# Main.net
KiCad netlist of a schematic drawn in Altium Designer
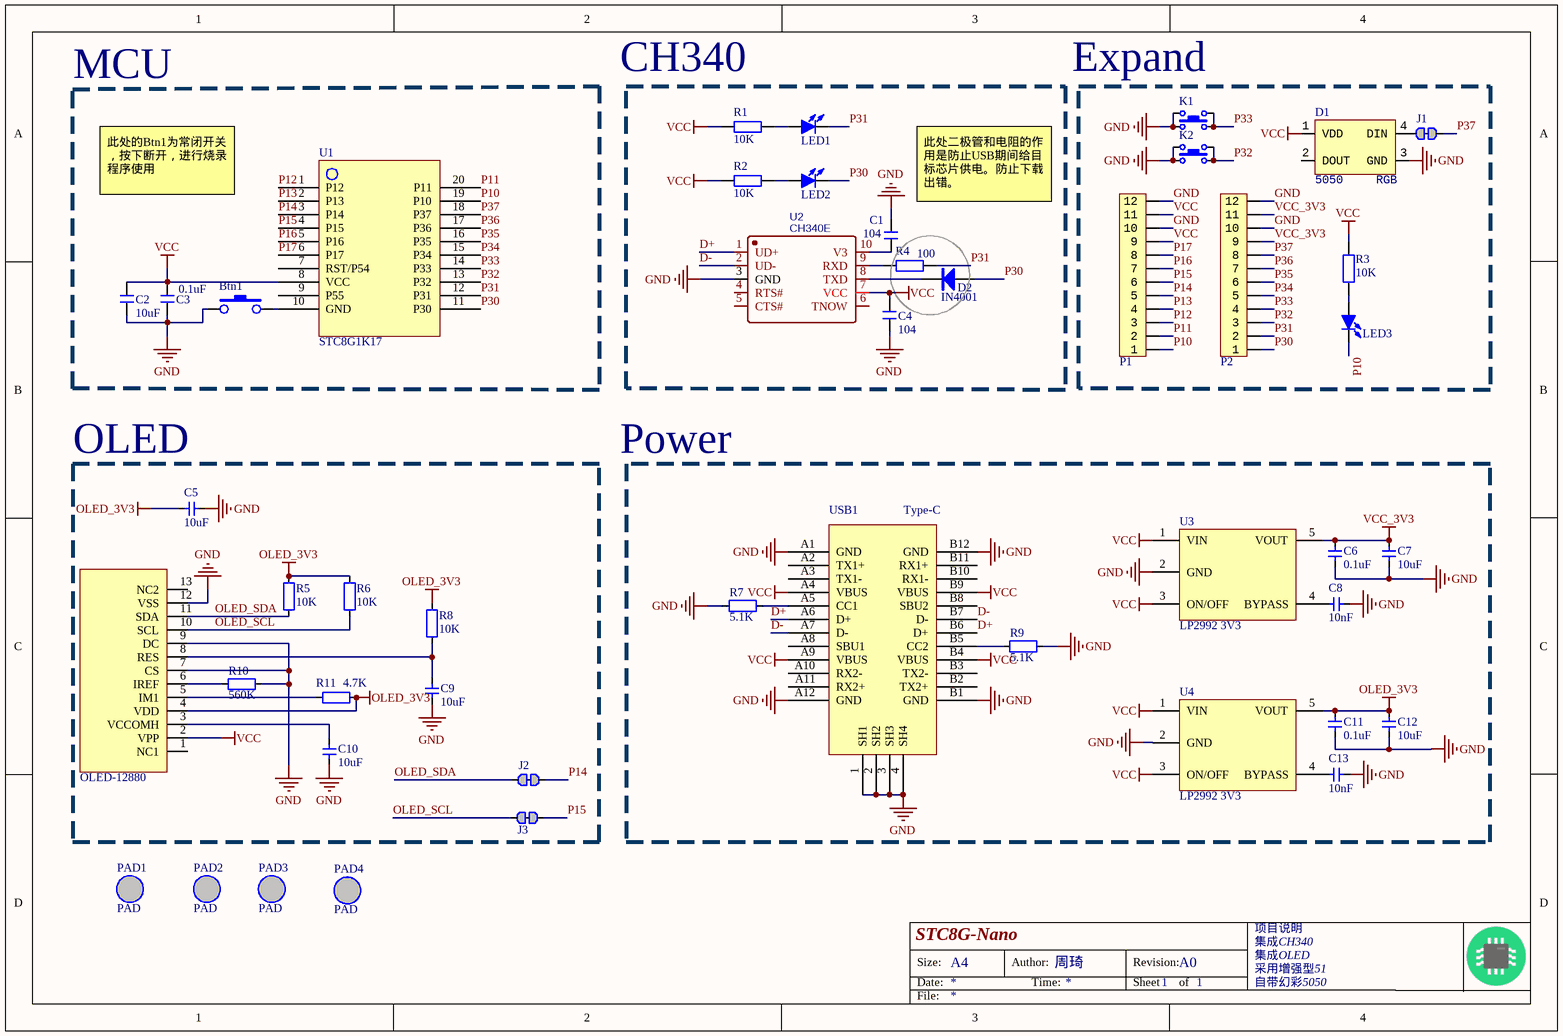
[diagram p0: Main.SchDoc]

(export (version "E")
  (design (tool "Eeschema 10.0.6"))
  (components
    (comp (ref "1")
      (value "OLED-12880")
      (footprint "OLED-12880")
      (libsource (lib "mLib") (part "OLED-12880"))
    )
    (comp (ref "Btn1") (value "KEY") (footprint "TSW SMD-3*6*2.5") (libsource (lib "常用元件库") (part "KEY")))
    (comp (ref "C1")
      (value "104")
      (footprint "C0402_L")
      (description "无极性贴片电容")
      (fields (field (name "版权归属") "源创客"))
      (libsource (lib "9-电阻-电容-电感") (part "C"))
    )
    (comp (ref "C2")
      (value "10uF")
      (footprint "C0402_L")
      (description "无极性贴片电容")
      (fields (field (name "版权归属") "源创客"))
      (libsource (lib "9-电阻-电容-电感") (part "C"))
    )
    (comp (ref "C3")
      (value "0.1uF")
      (footprint "C0402_L")
      (description "无极性贴片电容")
      (fields (field (name "版权归属") "源创客"))
      (libsource (lib "9-电阻-电容-电感") (part "C"))
    )
    (comp (ref "C4")
      (value "104")
      (footprint "C0402_L")
      (description "无极性贴片电容")
      (fields (field (name "版权归属") "源创客"))
      (libsource (lib "9-电阻-电容-电感") (part "C"))
    )
    (comp (ref "C5")
      (value "10uF")
      (footprint "CAP_0402")
      (description "Capacitor")
      (libsource (lib "MyPcbLib") (part "电容-0402"))
    )
    (comp (ref "C6")
      (value "0.1uF")
      (footprint "CAP_0402")
      (description "Capacitor")
      (libsource (lib "MyPcbLib") (part "电容-0402"))
    )
    (comp (ref "C7")
      (value "10uF")
      (footprint "CAP_0402")
      (description "Capacitor")
      (libsource (lib "MyPcbLib") (part "电容-0402"))
    )
    (comp (ref "C8")
      (value "10nF")
      (footprint "CAP_0402")
      (description "Capacitor")
      (libsource (lib "MyPcbLib") (part "电容-0402"))
    )
    (comp (ref "C9")
      (value "10uF")
      (footprint "CAP_0402")
      (description "Capacitor")
      (libsource (lib "MyPcbLib") (part "电容-0402"))
    )
    (comp (ref "C10")
      (value "10uF")
      (footprint "CAP_0402")
      (description "Capacitor")
      (libsource (lib "MyPcbLib") (part "电容-0402"))
    )
    (comp (ref "C11")
      (value "0.1uF")
      (footprint "CAP_0402")
      (description "Capacitor")
      (libsource (lib "MyPcbLib") (part "电容-0402"))
    )
    (comp (ref "C12")
      (value "10uF")
      (footprint "CAP_0402")
      (description "Capacitor")
      (libsource (lib "MyPcbLib") (part "电容-0402"))
    )
    (comp (ref "C13")
      (value "10nF")
      (footprint "CAP_0402")
      (description "Capacitor")
      (libsource (lib "MyPcbLib") (part "电容-0402"))
    )
    (comp (ref "D1")
      (value "RGB")
      (footprint "LED_5050_WS2812B")
      (description "LED")
      (fields (field (name "TYPE") "5050"))
      (libsource (lib "KitSprout") (part "LED_5050_WS2812B"))
    )
    (comp (ref "D2")
      (value "IN4001")
      (footprint "SOD-323")
      (description "整流二极管")
      (fields (field (name "版权归属") "源创客"))
      (libsource (lib "10-二极管-整流桥") (part "M7"))
    )
    (comp (ref "J1")
      (value "跳线")
      (footprint "RES_0402")
      (description "Resistor")
      (fields (field (name "PUBLISHER") "Altium Limited"))
      (libsource (lib "MyPcbLib") (part "跳线"))
    )
    (comp (ref "J2")
      (value "跳线")
      (footprint "RES_0402")
      (description "Resistor")
      (fields (field (name "PUBLISHER") "Altium Limited"))
      (libsource (lib "MyPcbLib") (part "跳线"))
    )
    (comp (ref "J3")
      (value "跳线")
      (footprint "RES_0402")
      (description "Resistor")
      (fields (field (name "PUBLISHER") "Altium Limited"))
      (libsource (lib "MyPcbLib") (part "跳线"))
    )
    (comp (ref "K1")
      (value "TACT 4P")
      (footprint "ButtonTACT_3.5*3.55_90")
      (description "Button")
      (libsource (lib "KitSprout") (part "ButtonTACT"))
    )
    (comp (ref "K2")
      (value "TACT 4P")
      (footprint "ButtonTACT_3.5*3.55_90")
      (description "Button")
      (libsource (lib "KitSprout") (part "ButtonTACT"))
    )
    (comp (ref "LED1")
      (value "红色")
      (footprint "LED0603_B")
      (description "贴片LED")
      (libsource (lib "0.3 - LED发光二极管") (part "LED-SMD"))
    )
    (comp (ref "LED2")
      (value "红色")
      (footprint "LED0603_B")
      (description "贴片LED")
      (libsource (lib "0.3 - LED发光二极管") (part "LED-SMD"))
    )
    (comp (ref "LED3")
      (value "红色")
      (footprint "LED0603_B")
      (description "贴片LED")
      (libsource (lib "0.3 - LED发光二极管") (part "LED-SMD"))
    )
    (comp (ref "P1")
      (value "HDR1x12_2.54")
      (footprint "HDR2.54-LI-12P")
      (description "Header")
      (libsource (lib "KitSprout") (part "HDR1x12_2.54"))
    )
    (comp (ref "P2")
      (value "HDR1x12_2.54")
      (footprint "HDR2.54-LI-12P")
      (description "Header")
      (libsource (lib "KitSprout") (part "HDR1x12_2.54"))
    )
    (comp (ref "PAD1")
      (value "PAD")
      (footprint "M2")
      (description "M2通孔")
      (libsource (lib "原理图库") (part "PAD"))
    )
    (comp (ref "PAD2")
      (value "PAD")
      (footprint "M2")
      (description "M2通孔")
      (libsource (lib "原理图库") (part "PAD"))
    )
    (comp (ref "PAD3")
      (value "PAD")
      (footprint "M2")
      (description "M2通孔")
      (libsource (lib "原理图库") (part "PAD"))
    )
    (comp (ref "PAD4")
      (value "PAD")
      (footprint "M2")
      (description "M2通孔")
      (libsource (lib "原理图库") (part "PAD"))
    )
    (comp (ref "R1")
      (value "10K")
      (footprint "RES_0402")
      (description "直插色环电阻")
      (fields (field (name "版权归属") "源创客"))
      (libsource (lib "9-电阻-电容-电感") (part "R-CRR"))
    )
    (comp (ref "R2")
      (value "10K")
      (footprint "RES_0402")
      (description "直插色环电阻")
      (fields (field (name "版权归属") "源创客"))
      (libsource (lib "9-电阻-电容-电感") (part "R-CRR"))
    )
    (comp (ref "R3")
      (value "10K")
      (footprint "RES_0402")
      (description "直插色环电阻")
      (fields (field (name "版权归属") "源创客"))
      (libsource (lib "9-电阻-电容-电感") (part "R-CRR"))
    )
    (comp (ref "R4")
      (value "100")
      (footprint "RES_0402")
      (description "直插色环电阻")
      (fields (field (name "版权归属") "源创客"))
      (libsource (lib "9-电阻-电容-电感") (part "R-CRR"))
    )
    (comp (ref "R5")
      (value "10K")
      (footprint "RES_0402")
      (description "Resistor")
      (libsource (lib "MyPcbLib") (part "电阻-0402"))
    )
    (comp (ref "R6")
      (value "10K")
      (footprint "RES_0402")
      (description "Resistor")
      (libsource (lib "MyPcbLib") (part "电阻-0402"))
    )
    (comp (ref "R7")
      (value "5.1K")
      (footprint "RES_0402")
      (description "Resistor")
      (libsource (lib "") (part "电阻-0402_1"))
    )
    (comp (ref "R8")
      (value "10K")
      (footprint "RES_0402")
      (description "Resistor")
      (libsource (lib "MyPcbLib") (part "电阻-0402"))
    )
    (comp (ref "R9")
      (value "5.1K")
      (footprint "RES_0402")
      (description "Resistor")
      (libsource (lib "") (part "电阻-0402_2"))
    )
    (comp (ref "R10")
      (value "560K")
      (footprint "RES_0402")
      (description "Resistor")
      (libsource (lib "") (part "电阻-0402_1"))
    )
    (comp (ref "R11")
      (value "4.7K")
      (footprint "RES_0402")
      (description "Resistor")
      (libsource (lib "") (part "电阻-0402_1"))
    )
    (comp (ref "U1") (value "STC8G1K17") (footprint "TSSOP20_L") (libsource (lib "原理图库") (part "STC8G1K17")))
    (comp (ref "U2")
      (value "CH340E")
      (footprint "MSOP10_M")
      (fields (field (name "BOM_SUPPLIER PART") "C99652") (field (name "SUBPART_NO") "1"))
      (libsource (lib "altium-import") (part "root_0_CH340E_"))
    )
    (comp (ref "U3")
      (value "LP2992 3V3")
      (footprint "SOT23-5")
      (description "LDO")
      (libsource (lib "MyPcbLib") (part "LP2992"))
    )
    (comp (ref "U4")
      (value "LP2992 3V3")
      (footprint "SOT23-5")
      (description "LDO")
      (libsource (lib "MyPcbLib") (part "LP2992"))
    )
    (comp (ref "USB1")
      (value "Type-C")
      (footprint "USB-C-SMD_16P")
      (libsource (lib "MyPcbLib") (part "USB-Type-C-TOP"))
    )
  )
  (nets
    (net (code "1") (name "/D+") (class "Default")
      (node (ref "U2") (pin "1") (pinfunction "UD+_1") (pintype "passive"))
      (node (ref "USB1") (pin "A6") (pinfunction "D+_A6") (pintype "passive"))
      (node (ref "USB1") (pin "B6") (pinfunction "D+_B6") (pintype "passive"))
    )
    (net (code "2") (name "/D-") (class "Default")
      (node (ref "U2") (pin "2") (pinfunction "UD-_2") (pintype "passive"))
      (node (ref "USB1") (pin "A7") (pinfunction "D-_A7") (pintype "passive"))
      (node (ref "USB1") (pin "B7") (pinfunction "D-_B7") (pintype "passive"))
    )
    (net (code "3") (name "/OLED_SCL") (class "Default")
      (node (ref "1") (pin "10") (pinfunction "SCL_10") (pintype "passive"))
      (node (ref "J3") (pin "1") (pinfunction "1_1") (pintype "passive"))
      (node (ref "R6") (pin "1") (pinfunction "1_1") (pintype "passive"))
    )
    (net (code "4") (name "/OLED_SDA") (class "Default")
      (node (ref "1") (pin "11") (pinfunction "SDA_11") (pintype "passive"))
      (node (ref "J2") (pin "1") (pinfunction "1_1") (pintype "passive"))
      (node (ref "R5") (pin "1") (pinfunction "1_1") (pintype "passive"))
    )
    (net (code "5") (name "/P10") (class "Default")
      (node (ref "LED3") (pin "2") (pinfunction "K_2") (pintype "passive"))
      (node (ref "P1") (pin "1") (pinfunction "1_1") (pintype "passive"))
      (node (ref "U1") (pin "19") (pinfunction "P10_19") (pintype "passive"))
    )
    (net (code "6") (name "/P11") (class "Default")
      (node (ref "P1") (pin "2") (pinfunction "2_2") (pintype "passive"))
      (node (ref "U1") (pin "20") (pinfunction "P11_20") (pintype "passive"))
    )
    (net (code "7") (name "/P12") (class "Default")
      (node (ref "P1") (pin "3") (pinfunction "3_3") (pintype "passive"))
      (node (ref "U1") (pin "1") (pinfunction "P12_1") (pintype "passive"))
    )
    (net (code "8") (name "/P13") (class "Default")
      (node (ref "P1") (pin "4") (pinfunction "4_4") (pintype "passive"))
      (node (ref "U1") (pin "2") (pinfunction "P13_2") (pintype "passive"))
    )
    (net (code "9") (name "/P14") (class "Default")
      (node (ref "J2") (pin "2") (pinfunction "2_2") (pintype "passive"))
      (node (ref "P1") (pin "5") (pinfunction "5_5") (pintype "passive"))
      (node (ref "U1") (pin "3") (pinfunction "P14_3") (pintype "passive"))
    )
    (net (code "10") (name "/P15") (class "Default")
      (node (ref "J3") (pin "2") (pinfunction "2_2") (pintype "passive"))
      (node (ref "P1") (pin "6") (pinfunction "6_6") (pintype "passive"))
      (node (ref "U1") (pin "4") (pinfunction "P15_4") (pintype "passive"))
    )
    (net (code "11") (name "/P16") (class "Default")
      (node (ref "P1") (pin "7") (pinfunction "7_7") (pintype "passive"))
      (node (ref "U1") (pin "5") (pinfunction "P16_5") (pintype "passive"))
    )
    (net (code "12") (name "/P17") (class "Default")
      (node (ref "P1") (pin "8") (pinfunction "8_8") (pintype "passive"))
      (node (ref "U1") (pin "6") (pinfunction "P17_6") (pintype "passive"))
    )
    (net (code "13") (name "/P30") (class "Default")
      (node (ref "D2") (pin "1") (pinfunction "A_1") (pintype "passive"))
      (node (ref "LED2") (pin "2") (pinfunction "K_2") (pintype "passive"))
      (node (ref "P2") (pin "1") (pinfunction "1_1") (pintype "passive"))
      (node (ref "U1") (pin "11") (pinfunction "P30_11") (pintype "passive"))
    )
    (net (code "14") (name "/P31") (class "Default")
      (node (ref "LED1") (pin "2") (pinfunction "K_2") (pintype "passive"))
      (node (ref "P2") (pin "2") (pinfunction "2_2") (pintype "passive"))
      (node (ref "R4") (pin "1") (pinfunction "1_1") (pintype "passive"))
      (node (ref "U1") (pin "12") (pinfunction "P31_12") (pintype "passive"))
    )
    (net (code "15") (name "/P32") (class "Default")
      (node (ref "K2") (pin "2") (pinfunction "2_2") (pintype "passive"))
      (node (ref "K2") (pin "4") (pinfunction "4_4") (pintype "passive"))
      (node (ref "P2") (pin "3") (pinfunction "3_3") (pintype "passive"))
      (node (ref "U1") (pin "13") (pinfunction "P32_13") (pintype "passive"))
    )
    (net (code "16") (name "/P33") (class "Default")
      (node (ref "K1") (pin "2") (pinfunction "2_2") (pintype "passive"))
      (node (ref "K1") (pin "4") (pinfunction "4_4") (pintype "passive"))
      (node (ref "P2") (pin "4") (pinfunction "4_4") (pintype "passive"))
      (node (ref "U1") (pin "14") (pinfunction "P33_14") (pintype "passive"))
    )
    (net (code "17") (name "/P34") (class "Default")
      (node (ref "P2") (pin "5") (pinfunction "5_5") (pintype "passive"))
      (node (ref "U1") (pin "15") (pinfunction "P34_15") (pintype "passive"))
    )
    (net (code "18") (name "/P35") (class "Default")
      (node (ref "P2") (pin "6") (pinfunction "6_6") (pintype "passive"))
      (node (ref "U1") (pin "16") (pinfunction "P35_16") (pintype "passive"))
    )
    (net (code "19") (name "/P36") (class "Default")
      (node (ref "P2") (pin "7") (pinfunction "7_7") (pintype "passive"))
      (node (ref "U1") (pin "17") (pinfunction "P36_17") (pintype "passive"))
    )
    (net (code "20") (name "/P37") (class "Default")
      (node (ref "J1") (pin "2") (pinfunction "2_2") (pintype "passive"))
      (node (ref "P2") (pin "8") (pinfunction "8_8") (pintype "passive"))
      (node (ref "U1") (pin "18") (pinfunction "P37_18") (pintype "passive"))
    )
    (net (code "21") (name "GND") (class "Default")
      (node (ref "1") (pin "12") (pinfunction "VSS_12") (pintype "passive"))
      (node (ref "1") (pin "7") (pinfunction "CS_7") (pintype "passive"))
      (node (ref "1") (pin "9") (pinfunction "DC_9") (pintype "passive"))
      (node (ref "Btn1") (pin "1") (pinfunction "1_1") (pintype "passive"))
      (node (ref "C1") (pin "1") (pinfunction "1_1") (pintype "passive"))
      (node (ref "C10") (pin "1") (pinfunction "1_1") (pintype "passive"))
      (node (ref "C11") (pin "1") (pinfunction "1_1") (pintype "passive"))
      (node (ref "C12") (pin "1") (pinfunction "1_1") (pintype "passive"))
      (node (ref "C13") (pin "1") (pinfunction "1_1") (pintype "passive"))
      (node (ref "C2") (pin "1") (pinfunction "1_1") (pintype "passive"))
      (node (ref "C3") (pin "1") (pinfunction "1_1") (pintype "passive"))
      (node (ref "C4") (pin "2") (pinfunction "2_2") (pintype "passive"))
      (node (ref "C5") (pin "1") (pinfunction "1_1") (pintype "passive"))
      (node (ref "C6") (pin "1") (pinfunction "1_1") (pintype "passive"))
      (node (ref "C7") (pin "1") (pinfunction "1_1") (pintype "passive"))
      (node (ref "C8") (pin "1") (pinfunction "1_1") (pintype "passive"))
      (node (ref "C9") (pin "1") (pinfunction "1_1") (pintype "passive"))
      (node (ref "D1") (pin "3") (pinfunction "GND_3") (pintype "passive"))
      (node (ref "K1") (pin "1") (pinfunction "1_1") (pintype "passive"))
      (node (ref "K1") (pin "3") (pinfunction "3_3") (pintype "passive"))
      (node (ref "K2") (pin "1") (pinfunction "1_1") (pintype "passive"))
      (node (ref "K2") (pin "3") (pinfunction "3_3") (pintype "passive"))
      (node (ref "P1") (pin "10") (pinfunction "10_10") (pintype "passive"))
      (node (ref "P1") (pin "12") (pinfunction "12_12") (pintype "passive"))
      (node (ref "P2") (pin "10") (pinfunction "10_10") (pintype "passive"))
      (node (ref "P2") (pin "12") (pinfunction "12_12") (pintype "passive"))
      (node (ref "R10") (pin "2") (pinfunction "2_2") (pintype "passive"))
      (node (ref "R7") (pin "1") (pinfunction "1_1") (pintype "passive"))
      (node (ref "R9") (pin "1") (pinfunction "1_1") (pintype "passive"))
      (node (ref "U2") (pin "3") (pinfunction "GND_3") (pintype "passive"))
      (node (ref "U3") (pin "2") (pinfunction "GND_2") (pintype "passive"))
      (node (ref "U4") (pin "2") (pinfunction "GND_2") (pintype "passive"))
      (node (ref "USB1") (pin "1") (pinfunction "SH1_1") (pintype "passive"))
      (node (ref "USB1") (pin "2") (pinfunction "SH2_2") (pintype "passive"))
      (node (ref "USB1") (pin "3") (pinfunction "SH3_3") (pintype "passive"))
      (node (ref "USB1") (pin "4") (pinfunction "SH4_4") (pintype "passive"))
      (node (ref "USB1") (pin "A1") (pinfunction "GND_A1") (pintype "passive"))
      (node (ref "USB1") (pin "A12") (pinfunction "GND_A12") (pintype "passive"))
      (node (ref "USB1") (pin "B1") (pinfunction "GND_B1") (pintype "passive"))
      (node (ref "USB1") (pin "B12") (pinfunction "GND_B12") (pintype "passive"))
    )
    (net (code "22") (name "Net-(1-IM1)") (class "Default")
      (node (ref "1") (pin "5") (pinfunction "IM1_5") (pintype "passive"))
      (node (ref "R11") (pin "1") (pinfunction "1_1") (pintype "passive"))
    )
    (net (code "23") (name "Net-(1-IREF)") (class "Default")
      (node (ref "1") (pin "6") (pinfunction "IREF_6") (pintype "passive"))
      (node (ref "R10") (pin "1") (pinfunction "1_1") (pintype "passive"))
    )
    (net (code "24") (name "Net-(1-RES)") (class "Default")
      (node (ref "1") (pin "8") (pinfunction "RES_8") (pintype "passive"))
      (node (ref "C9") (pin "2") (pinfunction "2_2") (pintype "passive"))
      (node (ref "R8") (pin "1") (pinfunction "1_1") (pintype "passive"))
    )
    (net (code "25") (name "Net-(1-VCCOMH)") (class "Default")
      (node (ref "1") (pin "3") (pinfunction "VCCOMH_3") (pintype "passive"))
      (node (ref "C10") (pin "2") (pinfunction "2_2") (pintype "passive"))
    )
    (net (code "26") (name "Net-(D1-DIN)") (class "Default")
      (node (ref "D1") (pin "4") (pinfunction "DIN_4") (pintype "passive"))
      (node (ref "J1") (pin "1") (pinfunction "1_1") (pintype "passive"))
    )
    (net (code "27") (name "Net-(D2-K)") (class "Default")
      (node (ref "D2") (pin "2") (pinfunction "K_2") (pintype "passive"))
      (node (ref "U2") (pin "8") (pinfunction "TXD_8") (pintype "passive"))
    )
    (net (code "28") (name "Net-(LED1-A)") (class "Default")
      (node (ref "LED1") (pin "1") (pinfunction "A_1") (pintype "passive"))
      (node (ref "R1") (pin "1") (pinfunction "1_1") (pintype "passive"))
    )
    (net (code "29") (name "Net-(LED2-A)") (class "Default")
      (node (ref "LED2") (pin "1") (pinfunction "A_1") (pintype "passive"))
      (node (ref "R2") (pin "1") (pinfunction "1_1") (pintype "passive"))
    )
    (net (code "30") (name "Net-(LED3-A)") (class "Default")
      (node (ref "LED3") (pin "1") (pinfunction "A_1") (pintype "passive"))
      (node (ref "R3") (pin "1") (pinfunction "1_1") (pintype "passive"))
    )
    (net (code "31") (name "Net-(U1-GND)") (class "Default")
      (node (ref "Btn1") (pin "2") (pinfunction "2_2") (pintype "passive"))
      (node (ref "U1") (pin "10") (pinfunction "GND_10") (pintype "passive"))
    )
    (net (code "32") (name "Net-(U2-RXD)") (class "Default")
      (node (ref "R4") (pin "2") (pinfunction "2_2") (pintype "passive"))
      (node (ref "U2") (pin "9") (pinfunction "RXD_9") (pintype "passive"))
    )
    (net (code "33") (name "Net-(U2-V3)") (class "Default")
      (node (ref "C1") (pin "2") (pinfunction "2_2") (pintype "passive"))
      (node (ref "U2") (pin "10") (pinfunction "V3_10") (pintype "passive"))
    )
    (net (code "34") (name "Net-(U3-BYPASS)") (class "Default")
      (node (ref "C8") (pin "2") (pinfunction "2_2") (pintype "passive"))
      (node (ref "U3") (pin "4") (pinfunction "BYPASS_4") (pintype "passive"))
    )
    (net (code "35") (name "Net-(U4-BYPASS)") (class "Default")
      (node (ref "C13") (pin "2") (pinfunction "2_2") (pintype "passive"))
      (node (ref "U4") (pin "4") (pinfunction "BYPASS_4") (pintype "passive"))
    )
    (net (code "36") (name "Net-(USB1-CC1)") (class "Default")
      (node (ref "R7") (pin "2") (pinfunction "2_2") (pintype "passive"))
      (node (ref "USB1") (pin "A5") (pinfunction "CC1_A5") (pintype "passive"))
    )
    (net (code "37") (name "Net-(USB1-CC2)") (class "Default")
      (node (ref "R9") (pin "2") (pinfunction "2_2") (pintype "passive"))
      (node (ref "USB1") (pin "B5") (pinfunction "CC2_B5") (pintype "passive"))
    )
    (net (code "38") (name "OLED_3V3") (class "Default")
      (node (ref "1") (pin "4") (pinfunction "VDD_4") (pintype "passive"))
      (node (ref "C11") (pin "2") (pinfunction "2_2") (pintype "passive"))
      (node (ref "C12") (pin "2") (pinfunction "2_2") (pintype "passive"))
      (node (ref "C5") (pin "2") (pinfunction "2_2") (pintype "passive"))
      (node (ref "R11") (pin "2") (pinfunction "2_2") (pintype "passive"))
      (node (ref "R5") (pin "2") (pinfunction "2_2") (pintype "passive"))
      (node (ref "R6") (pin "2") (pinfunction "2_2") (pintype "passive"))
      (node (ref "R8") (pin "2") (pinfunction "2_2") (pintype "passive"))
      (node (ref "U4") (pin "5") (pinfunction "VOUT_5") (pintype "passive"))
    )
    (net (code "39") (name "VCC") (class "Default")
      (node (ref "1") (pin "2") (pinfunction "VPP_2") (pintype "passive"))
      (node (ref "C2") (pin "2") (pinfunction "2_2") (pintype "passive"))
      (node (ref "C3") (pin "2") (pinfunction "2_2") (pintype "passive"))
      (node (ref "C4") (pin "1") (pinfunction "1_1") (pintype "passive"))
      (node (ref "D1") (pin "1") (pinfunction "VDD_1") (pintype "passive"))
      (node (ref "P1") (pin "11") (pinfunction "11_11") (pintype "passive"))
      (node (ref "P1") (pin "9") (pinfunction "9_9") (pintype "passive"))
      (node (ref "R1") (pin "2") (pinfunction "2_2") (pintype "passive"))
      (node (ref "R2") (pin "2") (pinfunction "2_2") (pintype "passive"))
      (node (ref "R3") (pin "2") (pinfunction "2_2") (pintype "passive"))
      (node (ref "U1") (pin "8") (pinfunction "VCC_8") (pintype "passive"))
      (node (ref "U2") (pin "7") (pinfunction "VCC_7") (pintype "passive"))
      (node (ref "U3") (pin "1") (pinfunction "VIN_1") (pintype "passive"))
      (node (ref "U3") (pin "3") (pinfunction "ON/OFF_3") (pintype "passive"))
      (node (ref "U4") (pin "1") (pinfunction "VIN_1") (pintype "passive"))
      (node (ref "U4") (pin "3") (pinfunction "ON/OFF_3") (pintype "passive"))
      (node (ref "USB1") (pin "A4") (pinfunction "VBUS_A4") (pintype "passive"))
      (node (ref "USB1") (pin "A9") (pinfunction "VBUS_A9") (pintype "passive"))
      (node (ref "USB1") (pin "B4") (pinfunction "VBUS_B4") (pintype "passive"))
      (node (ref "USB1") (pin "B9") (pinfunction "VBUS_B9") (pintype "passive"))
    )
    (net (code "40") (name "VCC_3V3") (class "Default")
      (node (ref "C6") (pin "2") (pinfunction "2_2") (pintype "passive"))
      (node (ref "C7") (pin "2") (pinfunction "2_2") (pintype "passive"))
      (node (ref "P2") (pin "11") (pinfunction "11_11") (pintype "passive"))
      (node (ref "P2") (pin "9") (pinfunction "9_9") (pintype "passive"))
      (node (ref "U3") (pin "5") (pinfunction "VOUT_5") (pintype "passive"))
    )
    (net (code "41") (name "unconnected-(1-NC1-Pad1)") (class "Default")
      (node (ref "1") (pin "1") (pinfunction "NC1_1") (pintype "passive"))
    )
    (net (code "42") (name "unconnected-(1-NC2-Pad13)") (class "Default")
      (node (ref "1") (pin "13") (pinfunction "NC2_13") (pintype "passive"))
    )
    (net (code "43") (name "unconnected-(D1-DOUT-Pad2)") (class "Default")
      (node (ref "D1") (pin "2") (pinfunction "DOUT_2") (pintype "passive"))
    )
    (net (code "44") (name "unconnected-(U1-P55-Pad9)") (class "Default")
      (node (ref "U1") (pin "9") (pinfunction "P55_9") (pintype "passive"))
    )
    (net (code "45") (name "unconnected-(U1-RST{slash}P54-Pad7)") (class "Default")
      (node (ref "U1") (pin "7") (pinfunction "RST/P54_7") (pintype "passive"))
    )
    (net (code "46") (name "unconnected-(U2-CTS#-Pad5)") (class "Default")
      (node (ref "U2") (pin "5") (pinfunction "CTS#_5") (pintype "passive"))
    )
    (net (code "47") (name "unconnected-(U2-RTS#-Pad4)") (class "Default")
      (node (ref "U2") (pin "4") (pinfunction "RTS#_4") (pintype "passive"))
    )
    (net (code "48") (name "unconnected-(U2-TNOW-Pad6)") (class "Default")
      (node (ref "U2") (pin "6") (pinfunction "TNOW_6") (pintype "passive"))
    )
    (net (code "49") (name "unconnected-(USB1-RX1+-PadB11)") (class "Default")
      (node (ref "USB1") (pin "B11") (pinfunction "RX1+_B11") (pintype "passive"))
    )
    (net (code "50") (name "unconnected-(USB1-RX1--PadB10)") (class "Default")
      (node (ref "USB1") (pin "B10") (pinfunction "RX1-_B10") (pintype "passive"))
    )
    (net (code "51") (name "unconnected-(USB1-RX2+-PadA11)") (class "Default")
      (node (ref "USB1") (pin "A11") (pinfunction "RX2+_A11") (pintype "passive"))
    )
    (net (code "52") (name "unconnected-(USB1-RX2--PadA10)") (class "Default")
      (node (ref "USB1") (pin "A10") (pinfunction "RX2-_A10") (pintype "passive"))
    )
    (net (code "53") (name "unconnected-(USB1-SBU1-PadA8)") (class "Default")
      (node (ref "USB1") (pin "A8") (pinfunction "SBU1_A8") (pintype "passive"))
    )
    (net (code "54") (name "unconnected-(USB1-SBU2-PadB8)") (class "Default")
      (node (ref "USB1") (pin "B8") (pinfunction "SBU2_B8") (pintype "passive"))
    )
    (net (code "55") (name "unconnected-(USB1-TX1+-PadA2)") (class "Default")
      (node (ref "USB1") (pin "A2") (pinfunction "TX1+_A2") (pintype "passive"))
    )
    (net (code "56") (name "unconnected-(USB1-TX1--PadA3)") (class "Default")
      (node (ref "USB1") (pin "A3") (pinfunction "TX1-_A3") (pintype "passive"))
    )
    (net (code "57") (name "unconnected-(USB1-TX2+-PadB2)") (class "Default")
      (node (ref "USB1") (pin "B2") (pinfunction "TX2+_B2") (pintype "passive"))
    )
    (net (code "58") (name "unconnected-(USB1-TX2--PadB3)") (class "Default")
      (node (ref "USB1") (pin "B3") (pinfunction "TX2-_B3") (pintype "passive"))
    )
  )
)
